# Sensores_3.net
KiCad netlist of a schematic drawn in Altium Designer
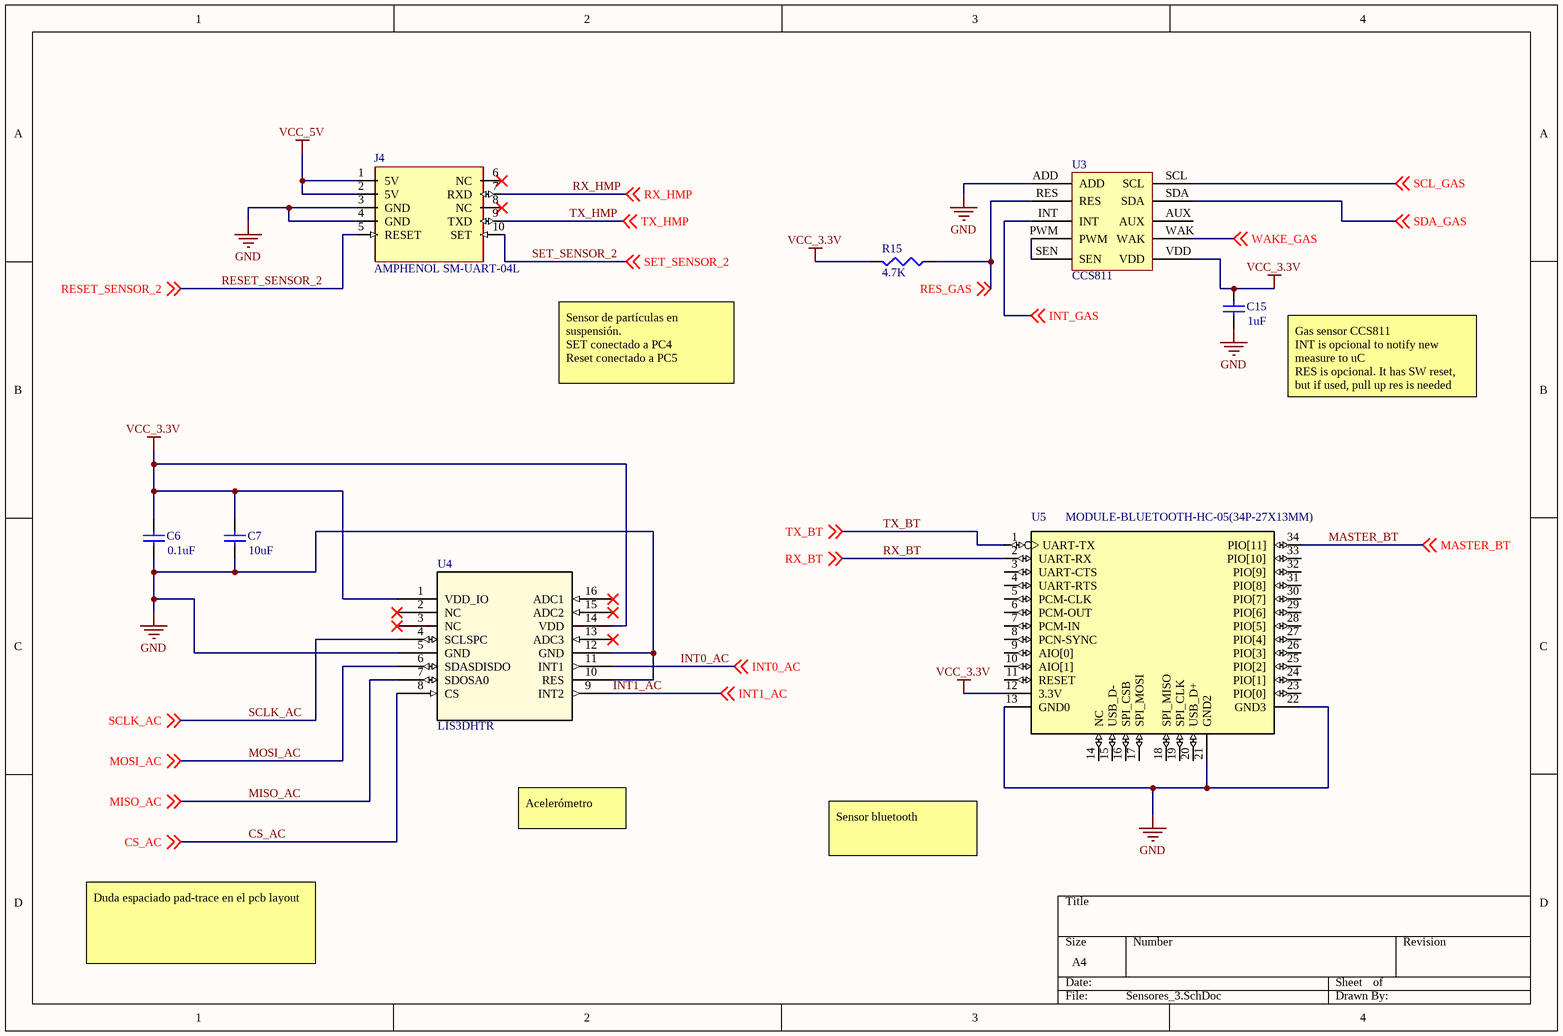
[diagram p0: Sensores_3.SchDoc]

(export (version "E")
  (design (tool "Eeschema 10.0.6"))
  (components
    (comp (ref "C6")
      (value "0.1uF")
      (footprint "0603")
      (description "Capacitor")
      (fields (field (name "Comment") "Cap") (field (name "PUBLISHER") "Altium Limited"))
      (libsource (lib "Bicimaps") (part "Cap_0603"))
    )
    (comp (ref "C7")
      (value "10uF")
      (footprint "0603")
      (description "Capacitor")
      (fields (field (name "Comment") "Cap") (field (name "PUBLISHER") "Altium Limited"))
      (libsource (lib "Bicimaps") (part "Cap_0603"))
    )
    (comp (ref "C15")
      (value "1uF")
      (footprint "0603")
      (description "Capacitor")
      (fields (field (name "Comment") "Cap") (field (name "PUBLISHER") "Altium Limited"))
      (libsource (lib "Bicimaps") (part "Cap_0603"))
    )
    (comp (ref "J4")
      (value "AMPHENOL SM-UART-04L")
      (footprint "PM SENSOR")
      (libsource (lib "Bicimaps") (part "AMPHENOL"))
    )
    (comp (ref "R15")
      (value "4.7K")
      (footprint "0603")
      (description "Resistor")
      (fields (field (name "Comment") "Res3") (field (name "PUBLISHER") "Altium Limited"))
      (libsource (lib "Miscellaneous Devices") (part "Res3"))
    )
    (comp (ref "U3") (value "CCS811") (footprint "CCS811") (libsource (lib "Bicimaps") (part "CCS811")))
    (comp (ref "U4")
      (value "LIS3DHTR")
      (footprint "LIS3DHTR")
      (description "Imported")
      (libsource (lib "Bicimaps") (part "LIS3DHTR"))
    )
    (comp (ref "U5")
      (value "MODULE-BLUETOOTH-HC-05(34P-27X13MM)")
      (footprint "HC-05")
      (description "Modulo bluetooth, 34 pin")
      (fields (field (name "MF") "Texas Instruments") (field (name "MP") "HC05"))
      (libsource (lib "Bicimaps") (part "HC-05 (Bluetooth module)"))
    )
  )
  (nets
    (net (code "1") (name "CS_AC") (class "Default")
      (node (ref "U4") (pin "8") (pinfunction "CS_8") (pintype "input"))
    )
    (net (code "2") (name "GND") (class "Default")
      (node (ref "C15") (pin "1") (pinfunction "1_1") (pintype "passive"))
      (node (ref "C6") (pin "1") (pinfunction "1_1") (pintype "passive"))
      (node (ref "C7") (pin "1") (pinfunction "1_1") (pintype "passive"))
      (node (ref "J4") (pin "3") (pinfunction "GND_3") (pintype "power_in"))
      (node (ref "J4") (pin "4") (pinfunction "GND_4") (pintype "power_in"))
      (node (ref "U3") (pin "ADD") (pinfunction "ADD_ADD") (pintype "passive"))
      (node (ref "U4") (pin "10") (pinfunction "RES_10") (pintype "passive"))
      (node (ref "U4") (pin "12") (pinfunction "GND_12") (pintype "power_in"))
      (node (ref "U4") (pin "5") (pinfunction "GND_5") (pintype "power_in"))
      (node (ref "U5") (pin "13") (pinfunction "GND0_13") (pintype "power_in"))
      (node (ref "U5") (pin "21") (pinfunction "GND2_21") (pintype "power_in"))
      (node (ref "U5") (pin "22") (pinfunction "GND3_22") (pintype "power_in"))
    )
    (net (code "3") (name "INT0_AC") (class "Default")
      (node (ref "U4") (pin "11") (pinfunction "INT1_11") (pintype "output"))
    )
    (net (code "4") (name "INT1_AC") (class "Default")
      (node (ref "U4") (pin "9") (pinfunction "INT2_9") (pintype "output"))
    )
    (net (code "5") (name "INT_GAS") (class "Default")
      (node (ref "U3") (pin "INT") (pinfunction "INT_INT") (pintype "passive"))
    )
    (net (code "6") (name "MASTER_BT") (class "Default")
      (node (ref "U5") (pin "34") (pinfunction "PIO[11]_34") (pintype "bidirectional"))
    )
    (net (code "7") (name "MISO_AC") (class "Default")
      (node (ref "U4") (pin "7") (pinfunction "SDOSA0_7") (pintype "bidirectional"))
    )
    (net (code "8") (name "MOSI_AC") (class "Default")
      (node (ref "U4") (pin "6") (pinfunction "SDASDISDO_6") (pintype "bidirectional"))
    )
    (net (code "9") (name "Net-(U3-PadPWM)") (class "Default")
      (node (ref "U3") (pin "PWM") (pinfunction "PWM_PWM") (pintype "passive"))
      (node (ref "U3") (pin "SEN") (pinfunction "SEN_SEN") (pintype "passive"))
    )
    (net (code "10") (name "RESET_SENSOR_2") (class "Default")
      (node (ref "J4") (pin "5") (pinfunction "RESET_5") (pintype "input"))
    )
    (net (code "11") (name "RES_GAS") (class "Default")
      (node (ref "R15") (pin "1") (pinfunction "1_1") (pintype "passive"))
      (node (ref "U3") (pin "RES") (pinfunction "RES_RES") (pintype "passive"))
    )
    (net (code "12") (name "RX_BT") (class "Default")
      (node (ref "U5") (pin "2") (pinfunction "UART-RX_2") (pintype "bidirectional"))
    )
    (net (code "13") (name "RX_HMP") (class "Default")
      (node (ref "J4") (pin "7") (pinfunction "RXD_7") (pintype "bidirectional"))
    )
    (net (code "14") (name "SCLK_AC") (class "Default")
      (node (ref "U4") (pin "4") (pinfunction "SCLSPC_4") (pintype "bidirectional"))
    )
    (net (code "15") (name "SCL_GAS") (class "Default")
      (node (ref "U3") (pin "SCL") (pinfunction "SCL_SCL") (pintype "passive"))
    )
    (net (code "16") (name "SDA_GAS") (class "Default")
      (node (ref "U3") (pin "SDA") (pinfunction "SDA_SDA") (pintype "passive"))
    )
    (net (code "17") (name "SET_SENSOR_2") (class "Default")
      (node (ref "J4") (pin "10") (pinfunction "SET_10") (pintype "input"))
    )
    (net (code "18") (name "TX_BT") (class "Default")
      (node (ref "U5") (pin "1") (pinfunction "UART-TX_1") (pintype "bidirectional"))
    )
    (net (code "19") (name "TX_HMP") (class "Default")
      (node (ref "J4") (pin "9") (pinfunction "TXD_9") (pintype "bidirectional"))
    )
    (net (code "20") (name "VCC_3.3V") (class "Default")
      (node (ref "C15") (pin "2") (pinfunction "2_2") (pintype "passive"))
      (node (ref "C6") (pin "2") (pinfunction "2_2") (pintype "passive"))
      (node (ref "C7") (pin "2") (pinfunction "2_2") (pintype "passive"))
      (node (ref "R15") (pin "2") (pinfunction "2_2") (pintype "passive"))
      (node (ref "U3") (pin "VDD") (pinfunction "VDD_VDD") (pintype "passive"))
      (node (ref "U4") (pin "1") (pinfunction "VDD_IO_1") (pintype "power_in"))
      (node (ref "U4") (pin "14") (pinfunction "VDD_14") (pintype "power_in"))
      (node (ref "U5") (pin "12") (pinfunction "3.3V_12") (pintype "power_in"))
    )
    (net (code "21") (name "VCC_5V") (class "Default")
      (node (ref "J4") (pin "1") (pinfunction "5V_1") (pintype "power_in"))
      (node (ref "J4") (pin "2") (pinfunction "5V_2") (pintype "power_in"))
    )
    (net (code "22") (name "WAKE_GAS") (class "Default")
      (node (ref "U3") (pin "WAK") (pinfunction "WAK_WAK") (pintype "passive"))
    )
    (net (code "23") (name "unconnected-(J4-NC-Pad6)") (class "Default")
      (node (ref "J4") (pin "6") (pinfunction "NC_6") (pintype "passive+no_connect"))
    )
    (net (code "24") (name "unconnected-(J4-NC-Pad8)") (class "Default")
      (node (ref "J4") (pin "8") (pinfunction "NC_8") (pintype "passive+no_connect"))
    )
    (net (code "25") (name "unconnected-(U3-PadAUX)") (class "Default")
      (node (ref "U3") (pin "AUX") (pinfunction "AUX_AUX") (pintype "passive"))
    )
    (net (code "26") (name "unconnected-(U4-ADC1-Pad16)") (class "Default")
      (node (ref "U4") (pin "16") (pinfunction "ADC1_16") (pintype "input+no_connect"))
    )
    (net (code "27") (name "unconnected-(U4-ADC2-Pad15)") (class "Default")
      (node (ref "U4") (pin "15") (pinfunction "ADC2_15") (pintype "input+no_connect"))
    )
    (net (code "28") (name "unconnected-(U4-ADC3-Pad13)") (class "Default")
      (node (ref "U4") (pin "13") (pinfunction "ADC3_13") (pintype "input+no_connect"))
    )
    (net (code "29") (name "unconnected-(U4-NC-Pad2)") (class "Default")
      (node (ref "U4") (pin "2") (pinfunction "NC_2") (pintype "passive+no_connect"))
    )
    (net (code "30") (name "unconnected-(U4-NC-Pad3)") (class "Default")
      (node (ref "U4") (pin "3") (pinfunction "NC_3") (pintype "passive+no_connect"))
    )
    (net (code "31") (name "unconnected-(U5-AIO[0]-Pad9)") (class "Default")
      (node (ref "U5") (pin "9") (pinfunction "AIO[0]_9") (pintype "bidirectional"))
    )
    (net (code "32") (name "unconnected-(U5-AIO[1]-Pad10)") (class "Default")
      (node (ref "U5") (pin "10") (pinfunction "AIO[1]_10") (pintype "bidirectional"))
    )
    (net (code "33") (name "unconnected-(U5-NC-Pad14)") (class "Default")
      (node (ref "U5") (pin "14") (pinfunction "NC_14") (pintype "bidirectional"))
    )
    (net (code "34") (name "unconnected-(U5-PCM-CLK-Pad5)") (class "Default")
      (node (ref "U5") (pin "5") (pinfunction "PCM-CLK_5") (pintype "bidirectional"))
    )
    (net (code "35") (name "unconnected-(U5-PCM-IN-Pad7)") (class "Default")
      (node (ref "U5") (pin "7") (pinfunction "PCM-IN_7") (pintype "bidirectional"))
    )
    (net (code "36") (name "unconnected-(U5-PCM-OUT-Pad6)") (class "Default")
      (node (ref "U5") (pin "6") (pinfunction "PCM-OUT_6") (pintype "bidirectional"))
    )
    (net (code "37") (name "unconnected-(U5-PCN-SYNC-Pad8)") (class "Default")
      (node (ref "U5") (pin "8") (pinfunction "PCN-SYNC_8") (pintype "bidirectional"))
    )
    (net (code "38") (name "unconnected-(U5-PIO[0]-Pad23)") (class "Default")
      (node (ref "U5") (pin "23") (pinfunction "PIO[0]_23") (pintype "bidirectional"))
    )
    (net (code "39") (name "unconnected-(U5-PIO[1]-Pad24)") (class "Default")
      (node (ref "U5") (pin "24") (pinfunction "PIO[1]_24") (pintype "bidirectional"))
    )
    (net (code "40") (name "unconnected-(U5-PIO[2]-Pad25)") (class "Default")
      (node (ref "U5") (pin "25") (pinfunction "PIO[2]_25") (pintype "bidirectional"))
    )
    (net (code "41") (name "unconnected-(U5-PIO[3]-Pad26)") (class "Default")
      (node (ref "U5") (pin "26") (pinfunction "PIO[3]_26") (pintype "bidirectional"))
    )
    (net (code "42") (name "unconnected-(U5-PIO[4]-Pad27)") (class "Default")
      (node (ref "U5") (pin "27") (pinfunction "PIO[4]_27") (pintype "bidirectional"))
    )
    (net (code "43") (name "unconnected-(U5-PIO[5]-Pad28)") (class "Default")
      (node (ref "U5") (pin "28") (pinfunction "PIO[5]_28") (pintype "bidirectional"))
    )
    (net (code "44") (name "unconnected-(U5-PIO[6]-Pad29)") (class "Default")
      (node (ref "U5") (pin "29") (pinfunction "PIO[6]_29") (pintype "bidirectional"))
    )
    (net (code "45") (name "unconnected-(U5-PIO[7]-Pad30)") (class "Default")
      (node (ref "U5") (pin "30") (pinfunction "PIO[7]_30") (pintype "bidirectional"))
    )
    (net (code "46") (name "unconnected-(U5-PIO[8]-Pad31)") (class "Default")
      (node (ref "U5") (pin "31") (pinfunction "PIO[8]_31") (pintype "bidirectional"))
    )
    (net (code "47") (name "unconnected-(U5-PIO[9]-Pad32)") (class "Default")
      (node (ref "U5") (pin "32") (pinfunction "PIO[9]_32") (pintype "bidirectional"))
    )
    (net (code "48") (name "unconnected-(U5-PIO[10]-Pad33)") (class "Default")
      (node (ref "U5") (pin "33") (pinfunction "PIO[10]_33") (pintype "bidirectional"))
    )
    (net (code "49") (name "unconnected-(U5-RESET-Pad11)") (class "Default")
      (node (ref "U5") (pin "11") (pinfunction "RESET_11") (pintype "bidirectional"))
    )
    (net (code "50") (name "unconnected-(U5-SPI_CLK-Pad19)") (class "Default")
      (node (ref "U5") (pin "19") (pinfunction "SPI_CLK_19") (pintype "bidirectional"))
    )
    (net (code "51") (name "unconnected-(U5-SPI_CSB-Pad16)") (class "Default")
      (node (ref "U5") (pin "16") (pinfunction "SPI_CSB_16") (pintype "bidirectional"))
    )
    (net (code "52") (name "unconnected-(U5-SPI_MISO-Pad18)") (class "Default")
      (node (ref "U5") (pin "18") (pinfunction "SPI_MISO_18") (pintype "bidirectional"))
    )
    (net (code "53") (name "unconnected-(U5-SPI_MOSI-Pad17)") (class "Default")
      (node (ref "U5") (pin "17") (pinfunction "SPI_MOSI_17") (pintype "bidirectional"))
    )
    (net (code "54") (name "unconnected-(U5-UART-CTS-Pad3)") (class "Default")
      (node (ref "U5") (pin "3") (pinfunction "UART-CTS_3") (pintype "bidirectional"))
    )
    (net (code "55") (name "unconnected-(U5-UART-RTS-Pad4)") (class "Default")
      (node (ref "U5") (pin "4") (pinfunction "UART-RTS_4") (pintype "bidirectional"))
    )
    (net (code "56") (name "unconnected-(U5-USB_D+-Pad20)") (class "Default")
      (node (ref "U5") (pin "20") (pinfunction "USB_D+_20") (pintype "bidirectional"))
    )
    (net (code "57") (name "unconnected-(U5-USB_D--Pad15)") (class "Default")
      (node (ref "U5") (pin "15") (pinfunction "USB_D-_15") (pintype "bidirectional"))
    )
  )
)
